# Main_Board_rev_A_-_hand_solder.net
KiCad netlist of a schematic drawn in EAGLE
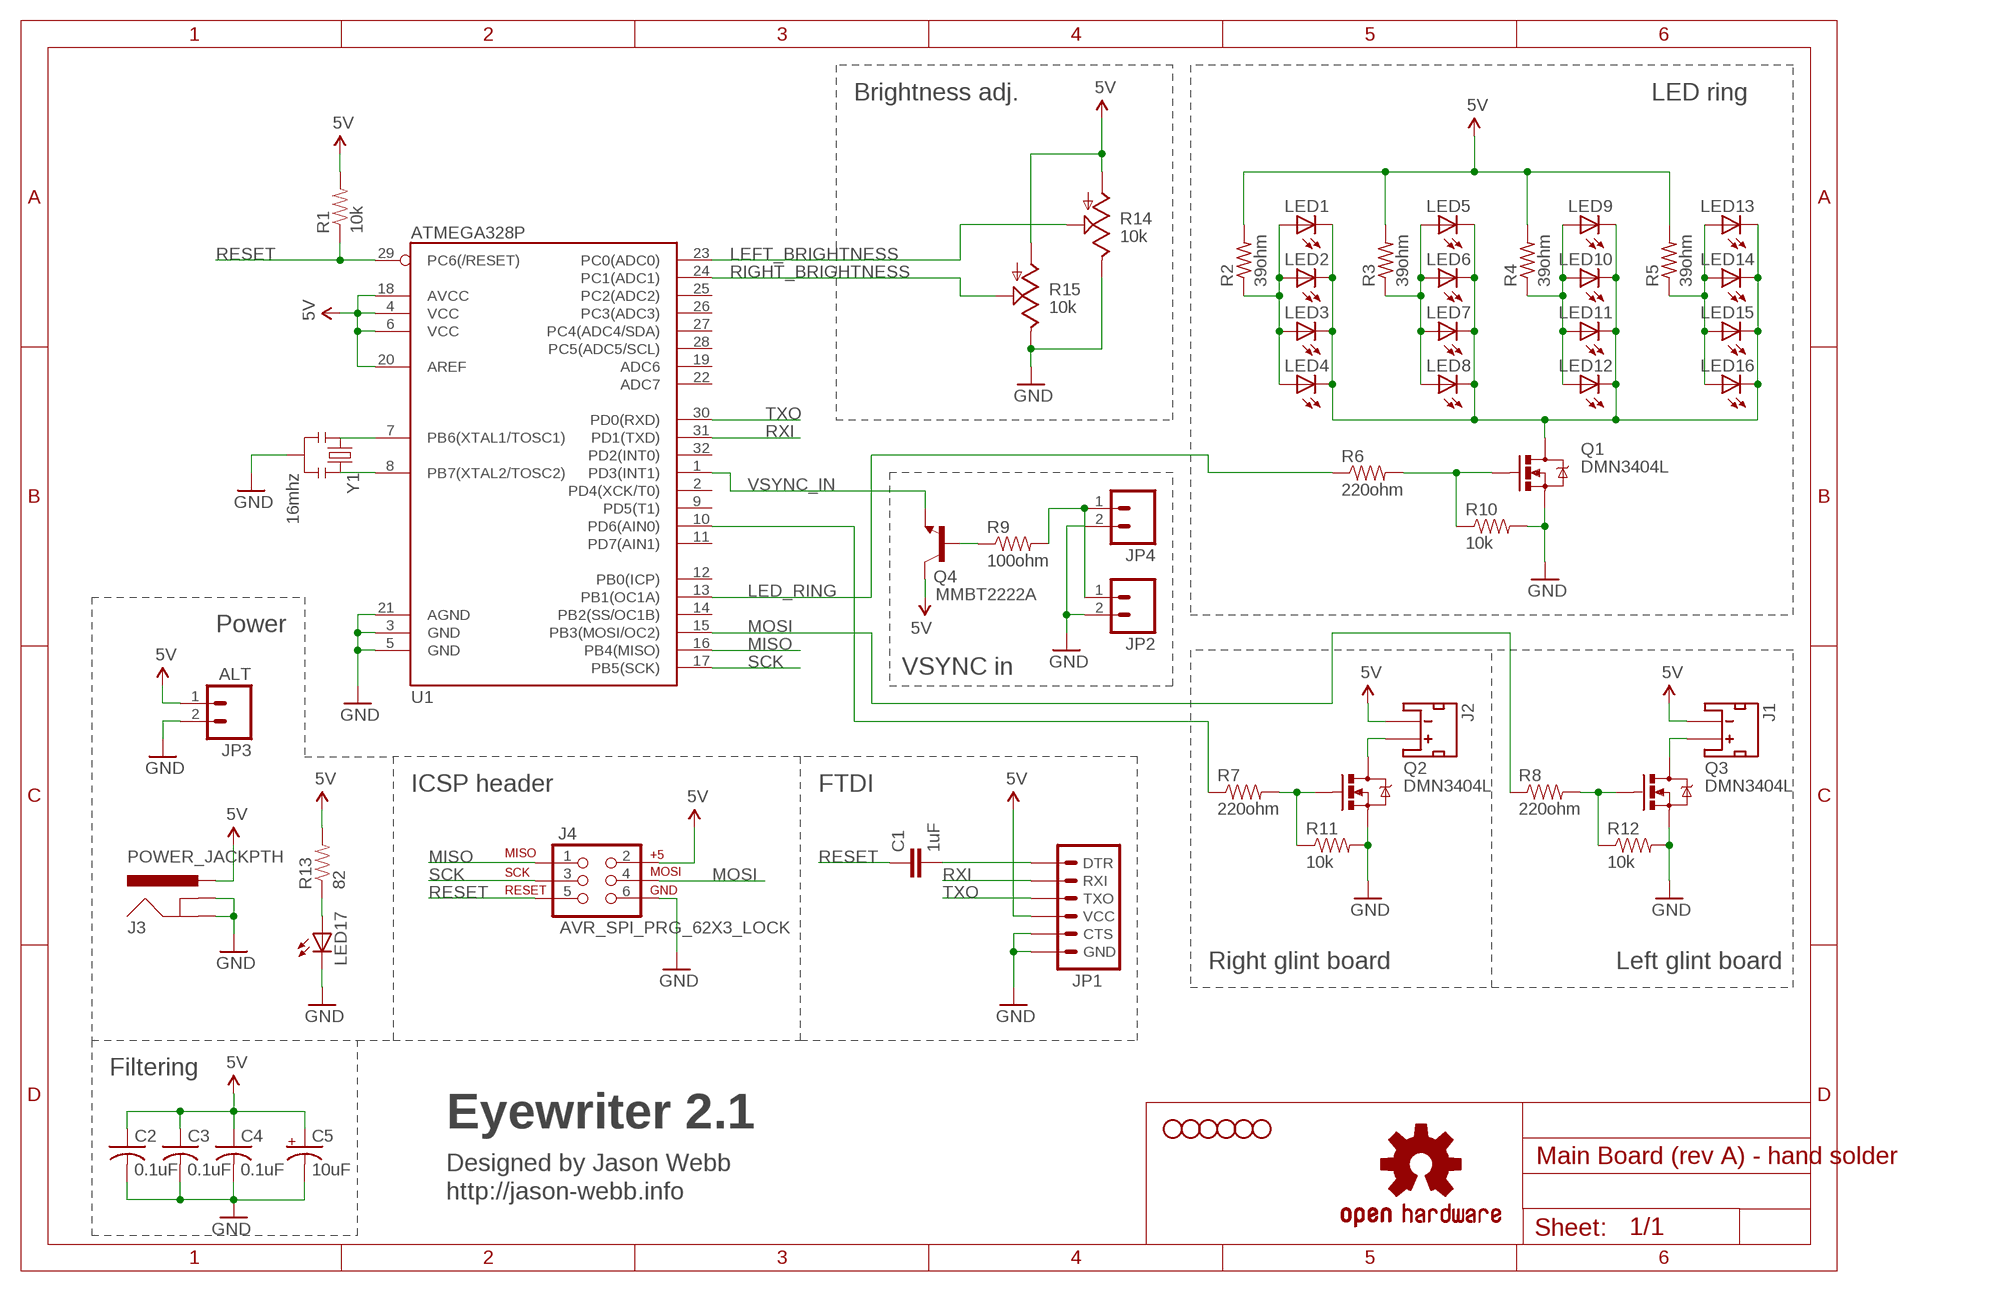
[diagram p0: schematic, sheet 1]

(export (version "E")
  (design (tool "Eeschema 10.0.6"))
  (components
    (comp (ref "C1")
      (value "1uF")
      (footprint "eagle-import:0805")
      (libsource (lib "eagle-import") (part "CAP0805"))
    )
    (comp (ref "C2")
      (value "0.1uF")
      (footprint "eagle-import:C0805K")
      (libsource (lib "eagle-import") (part "C-USC0805K"))
    )
    (comp (ref "C3")
      (value "0.1uF")
      (footprint "eagle-import:C0805K")
      (libsource (lib "eagle-import") (part "C-USC0805K"))
    )
    (comp (ref "C4")
      (value "0.1uF")
      (footprint "eagle-import:C0805K")
      (libsource (lib "eagle-import") (part "C-USC0805K"))
    )
    (comp (ref "C5")
      (value "10uF")
      (footprint "eagle-import:A_3216-18R")
      (libsource (lib "eagle-import") (part "CPOL-USA/3216-18R"))
    )
    (comp (ref "J1")
      (value "JST_2MM_MALE")
      (footprint "eagle-import:JST-2-SMD")
      (libsource (lib "eagle-import") (part "JST_2MM_MALE"))
    )
    (comp (ref "J2")
      (value "JST_2MM_MALE")
      (footprint "eagle-import:JST-2-SMD")
      (libsource (lib "eagle-import") (part "JST_2MM_MALE"))
    )
    (comp (ref "J3")
      (value "POWER_JACKPTH")
      (footprint "eagle-import:POWER_JACK_PTH")
      (libsource (lib "eagle-import") (part "POWER_JACKPTH"))
    )
    (comp (ref "J4")
      (value "AVR_SPI_PRG_62X3_LOCK")
      (footprint "eagle-import:2X3_LOCK")
      (libsource (lib "eagle-import") (part "AVR_SPI_PRG_62X3_LOCK"))
    )
    (comp (ref "JP1")
      (value "ARDUINO_SERIAL_PROGRAMLOCK")
      (footprint "eagle-import:1X06_LOCK")
      (libsource (lib "eagle-import") (part "ARDUINO_SERIAL_PROGRAMLOCK"))
    )
    (comp (ref "JP2")
      (value "M02PTH")
      (footprint "eagle-import:1X02")
      (libsource (lib "eagle-import") (part "M02PTH"))
    )
    (comp (ref "JP3")
      (value "ALT")
      (footprint "eagle-import:1X02")
      (libsource (lib "eagle-import") (part "M02PTH"))
    )
    (comp (ref "JP4")
      (value "M02PTH")
      (footprint "eagle-import:1X02")
      (libsource (lib "eagle-import") (part "M02PTH"))
    )
    (comp (ref "LED1")
      (value "LED5MM")
      (footprint "eagle-import:LED5MM")
      (libsource (lib "eagle-import") (part "LED5MM"))
    )
    (comp (ref "LED2")
      (value "LED5MM")
      (footprint "eagle-import:LED5MM")
      (libsource (lib "eagle-import") (part "LED5MM"))
    )
    (comp (ref "LED3")
      (value "LED5MM")
      (footprint "eagle-import:LED5MM")
      (libsource (lib "eagle-import") (part "LED5MM"))
    )
    (comp (ref "LED4")
      (value "LED5MM")
      (footprint "eagle-import:LED5MM")
      (libsource (lib "eagle-import") (part "LED5MM"))
    )
    (comp (ref "LED5")
      (value "LED5MM")
      (footprint "eagle-import:LED5MM")
      (libsource (lib "eagle-import") (part "LED5MM"))
    )
    (comp (ref "LED6")
      (value "LED5MM")
      (footprint "eagle-import:LED5MM")
      (libsource (lib "eagle-import") (part "LED5MM"))
    )
    (comp (ref "LED7")
      (value "LED5MM")
      (footprint "eagle-import:LED5MM")
      (libsource (lib "eagle-import") (part "LED5MM"))
    )
    (comp (ref "LED8")
      (value "LED5MM")
      (footprint "eagle-import:LED5MM")
      (libsource (lib "eagle-import") (part "LED5MM"))
    )
    (comp (ref "LED9")
      (value "LED5MM")
      (footprint "eagle-import:LED5MM")
      (libsource (lib "eagle-import") (part "LED5MM"))
    )
    (comp (ref "LED10")
      (value "LED5MM")
      (footprint "eagle-import:LED5MM")
      (libsource (lib "eagle-import") (part "LED5MM"))
    )
    (comp (ref "LED11")
      (value "LED5MM")
      (footprint "eagle-import:LED5MM")
      (libsource (lib "eagle-import") (part "LED5MM"))
    )
    (comp (ref "LED12")
      (value "LED5MM")
      (footprint "eagle-import:LED5MM")
      (libsource (lib "eagle-import") (part "LED5MM"))
    )
    (comp (ref "LED13")
      (value "LED5MM")
      (footprint "eagle-import:LED5MM")
      (libsource (lib "eagle-import") (part "LED5MM"))
    )
    (comp (ref "LED14")
      (value "LED5MM")
      (footprint "eagle-import:LED5MM")
      (libsource (lib "eagle-import") (part "LED5MM"))
    )
    (comp (ref "LED15")
      (value "LED5MM")
      (footprint "eagle-import:LED5MM")
      (libsource (lib "eagle-import") (part "LED5MM"))
    )
    (comp (ref "LED16")
      (value "LED5MM")
      (footprint "eagle-import:LED5MM")
      (libsource (lib "eagle-import") (part "LED5MM"))
    )
    (comp (ref "LED17")
      (value "LEDCHIPLED_0805")
      (footprint "eagle-import:CHIPLED_0805")
      (libsource (lib "eagle-import") (part "LEDCHIPLED_0805"))
    )
    (comp (ref "LOGO1")
      (value "OSHW-LOGOS")
      (footprint "eagle-import:OSHW-LOGO-S")
      (libsource (lib "eagle-import") (part "OSHW-LOGOS"))
    )
    (comp (ref "Q1")
      (value "DMN3404L")
      (footprint "eagle-import:SOT23-3")
      (libsource (lib "eagle-import") (part "MOSFET-NCHANNELSMD"))
    )
    (comp (ref "Q2")
      (value "DMN3404L")
      (footprint "eagle-import:SOT23-3")
      (libsource (lib "eagle-import") (part "MOSFET-NCHANNELSMD"))
    )
    (comp (ref "Q3")
      (value "DMN3404L")
      (footprint "eagle-import:SOT23-3")
      (libsource (lib "eagle-import") (part "MOSFET-NCHANNELSMD"))
    )
    (comp (ref "Q4")
      (value "MMBT2222A")
      (footprint "eagle-import:SOT23")
      (libsource (lib "eagle-import") (part "TRANSISTOR_NPNSOT23"))
    )
    (comp (ref "R1")
      (value "10k")
      (footprint "eagle-import:0805")
      (libsource (lib "eagle-import") (part "RESISTOR0805-RES"))
    )
    (comp (ref "R2")
      (value "39ohm")
      (footprint "eagle-import:0309_10")
      (libsource (lib "eagle-import") (part "R-US_0309/10"))
    )
    (comp (ref "R3")
      (value "39ohm")
      (footprint "eagle-import:0309_10")
      (libsource (lib "eagle-import") (part "R-US_0309/10"))
    )
    (comp (ref "R4")
      (value "39ohm")
      (footprint "eagle-import:0309_10")
      (libsource (lib "eagle-import") (part "R-US_0309/10"))
    )
    (comp (ref "R5")
      (value "39ohm")
      (footprint "eagle-import:0309_10")
      (libsource (lib "eagle-import") (part "R-US_0309/10"))
    )
    (comp (ref "R6")
      (value "220ohm")
      (footprint "eagle-import:0805")
      (libsource (lib "eagle-import") (part "RESISTOR0805-RES"))
    )
    (comp (ref "R7")
      (value "220ohm")
      (footprint "eagle-import:0805")
      (libsource (lib "eagle-import") (part "RESISTOR0805-RES"))
    )
    (comp (ref "R8")
      (value "220ohm")
      (footprint "eagle-import:0805")
      (libsource (lib "eagle-import") (part "RESISTOR0805-RES"))
    )
    (comp (ref "R9")
      (value "100ohm")
      (footprint "eagle-import:0805")
      (libsource (lib "eagle-import") (part "RESISTOR0805-RES"))
    )
    (comp (ref "R10")
      (value "10k")
      (footprint "eagle-import:0805")
      (libsource (lib "eagle-import") (part "RESISTOR0805-RES"))
    )
    (comp (ref "R11")
      (value "10k")
      (footprint "eagle-import:0805")
      (libsource (lib "eagle-import") (part "RESISTOR0805-RES"))
    )
    (comp (ref "R12")
      (value "10k")
      (footprint "eagle-import:0805")
      (libsource (lib "eagle-import") (part "RESISTOR0805-RES"))
    )
    (comp (ref "R13")
      (value "82")
      (footprint "eagle-import:0805")
      (libsource (lib "eagle-import") (part "RESISTOR0805-RES"))
    )
    (comp (ref "R14")
      (value "10k")
      (footprint "eagle-import:ALPS_POT")
      (libsource (lib "eagle-import") (part "POT"))
    )
    (comp (ref "R15")
      (value "10k")
      (footprint "eagle-import:ALPS_POT")
      (libsource (lib "eagle-import") (part "POT"))
    )
    (comp (ref "STANDOFF1")
      (value "STAND-OFF")
      (footprint "eagle-import:STAND-OFF")
      (libsource (lib "eagle-import") (part "STAND-OFF"))
    )
    (comp (ref "STANDOFF2")
      (value "STAND-OFF")
      (footprint "eagle-import:STAND-OFF")
      (libsource (lib "eagle-import") (part "STAND-OFF"))
    )
    (comp (ref "STANDOFF3")
      (value "STAND-OFF")
      (footprint "eagle-import:STAND-OFF")
      (libsource (lib "eagle-import") (part "STAND-OFF"))
    )
    (comp (ref "STANDOFF4")
      (value "STAND-OFF")
      (footprint "eagle-import:STAND-OFF")
      (libsource (lib "eagle-import") (part "STAND-OFF"))
    )
    (comp (ref "STANDOFF5")
      (value "STAND-OFF")
      (footprint "eagle-import:STAND-OFF")
      (libsource (lib "eagle-import") (part "STAND-OFF"))
    )
    (comp (ref "STANDOFF6")
      (value "STAND-OFF")
      (footprint "eagle-import:STAND-OFF")
      (libsource (lib "eagle-import") (part "STAND-OFF"))
    )
    (comp (ref "U1")
      (value "ATMEGA328P")
      (footprint "eagle-import:TQFP32-08")
      (libsource (lib "eagle-import") (part "ATMEGA328_SMT"))
    )
    (comp (ref "Y1")
      (value "16mhz")
      (footprint "eagle-import:RESONATOR-PTH")
      (libsource (lib "eagle-import") (part "RESONATORPTH"))
    )
  )
  (nets
    (net (code "1") (name "/LED_RING") (class "Default")
      (node (ref "R6") (pin "1") (pinfunction "1_1") (pintype "passive"))
      (node (ref "U1") (pin "13") (pinfunction "PB1(OC1A)_13") (pintype "bidirectional"))
    )
    (net (code "2") (name "/LEFT_BRIGHTNESS") (class "Default")
      (node (ref "R14") (pin "P$2") (pinfunction "S_P$2") (pintype "passive"))
      (node (ref "U1") (pin "23") (pinfunction "PC0(ADC0)_23") (pintype "bidirectional"))
    )
    (net (code "3") (name "/MISO") (class "Default")
      (node (ref "J4") (pin "1") (pinfunction "1_1") (pintype "passive"))
      (node (ref "U1") (pin "16") (pinfunction "PB4(MISO)_16") (pintype "bidirectional"))
    )
    (net (code "4") (name "/MOSI") (class "Default")
      (node (ref "J4") (pin "4") (pinfunction "4_4") (pintype "passive"))
      (node (ref "R7") (pin "1") (pinfunction "1_1") (pintype "passive"))
      (node (ref "U1") (pin "10") (pinfunction "PD6(AIN0)_10") (pintype "bidirectional"))
    )
    (net (code "5") (name "/RESET") (class "Default")
      (node (ref "C1") (pin "1") (pinfunction "1_1") (pintype "passive"))
      (node (ref "J4") (pin "5") (pinfunction "5_5") (pintype "passive"))
      (node (ref "R1") (pin "1") (pinfunction "1_1") (pintype "passive"))
      (node (ref "U1") (pin "29") (pinfunction "PC6(/RESET)_29") (pintype "bidirectional"))
    )
    (net (code "6") (name "/RIGHT_BRIGHTNESS") (class "Default")
      (node (ref "R15") (pin "P$2") (pinfunction "S_P$2") (pintype "passive"))
      (node (ref "U1") (pin "24") (pinfunction "PC1(ADC1)_24") (pintype "bidirectional"))
    )
    (net (code "7") (name "/RXI") (class "Default")
      (node (ref "JP1") (pin "2") (pinfunction "RXI_2") (pintype "passive"))
      (node (ref "U1") (pin "31") (pinfunction "PD1(TXD)_31") (pintype "bidirectional"))
    )
    (net (code "8") (name "/SCK") (class "Default")
      (node (ref "J4") (pin "3") (pinfunction "3_3") (pintype "passive"))
      (node (ref "U1") (pin "17") (pinfunction "PB5(SCK)_17") (pintype "bidirectional"))
    )
    (net (code "9") (name "/TXO") (class "Default")
      (node (ref "JP1") (pin "3") (pinfunction "TXO_3") (pintype "passive"))
      (node (ref "U1") (pin "30") (pinfunction "PD0(RXD)_30") (pintype "bidirectional"))
    )
    (net (code "10") (name "/VSYNC_IN") (class "Default")
      (node (ref "Q4") (pin "2") (pinfunction "E_2") (pintype "passive"))
      (node (ref "U1") (pin "1") (pinfunction "PD3(INT1)_1") (pintype "bidirectional"))
    )
    (net (code "11") (name "5V") (class "Default")
      (node (ref "C2") (pin "1") (pinfunction "1_1") (pintype "passive"))
      (node (ref "C3") (pin "1") (pinfunction "1_1") (pintype "passive"))
      (node (ref "C4") (pin "1") (pinfunction "1_1") (pintype "passive"))
      (node (ref "C5") (pin "+") (pinfunction "+_+") (pintype "passive"))
      (node (ref "J1") (pin "1") (pinfunction "-_1") (pintype "bidirectional"))
      (node (ref "J2") (pin "1") (pinfunction "-_1") (pintype "bidirectional"))
      (node (ref "J3") (pin "PWR") (pinfunction "PWR_PWR") (pintype "bidirectional"))
      (node (ref "J4") (pin "2") (pinfunction "2_2") (pintype "passive"))
      (node (ref "JP1") (pin "4") (pinfunction "VCC_4") (pintype "passive"))
      (node (ref "JP3") (pin "1") (pinfunction "1_1") (pintype "passive"))
      (node (ref "Q4") (pin "3") (pinfunction "C_3") (pintype "passive"))
      (node (ref "R1") (pin "2") (pinfunction "2_2") (pintype "passive"))
      (node (ref "R13") (pin "2") (pinfunction "2_2") (pintype "passive"))
      (node (ref "R14") (pin "P$3") (pinfunction "A_P$3") (pintype "passive"))
      (node (ref "R15") (pin "P$3") (pinfunction "A_P$3") (pintype "passive"))
      (node (ref "R2") (pin "2") (pinfunction "2_2") (pintype "passive"))
      (node (ref "R3") (pin "2") (pinfunction "2_2") (pintype "passive"))
      (node (ref "R4") (pin "2") (pinfunction "2_2") (pintype "passive"))
      (node (ref "R5") (pin "2") (pinfunction "2_2") (pintype "passive"))
      (node (ref "U1") (pin "18") (pinfunction "AVCC_18") (pintype "bidirectional"))
      (node (ref "U1") (pin "20") (pinfunction "AREF_20") (pintype "bidirectional"))
      (node (ref "U1") (pin "4") (pinfunction "VCC_4") (pintype "bidirectional"))
      (node (ref "U1") (pin "6") (pinfunction "VCC_6") (pintype "bidirectional"))
    )
    (net (code "12") (name "GND") (class "Default")
      (node (ref "C2") (pin "2") (pinfunction "2_2") (pintype "passive"))
      (node (ref "C3") (pin "2") (pinfunction "2_2") (pintype "passive"))
      (node (ref "C4") (pin "2") (pinfunction "2_2") (pintype "passive"))
      (node (ref "C5") (pin "-") (pinfunction "-_-") (pintype "passive"))
      (node (ref "J3") (pin "GND") (pinfunction "GND_GND") (pintype "bidirectional"))
      (node (ref "J3") (pin "GNDBREAK") (pinfunction "GNDBREAK_GNDBREAK") (pintype "bidirectional"))
      (node (ref "J4") (pin "6") (pinfunction "6_6") (pintype "passive"))
      (node (ref "JP1") (pin "5") (pinfunction "CTS_5") (pintype "passive"))
      (node (ref "JP1") (pin "6") (pinfunction "GND_6") (pintype "passive"))
      (node (ref "JP2") (pin "2") (pinfunction "2_2") (pintype "passive"))
      (node (ref "JP3") (pin "2") (pinfunction "2_2") (pintype "passive"))
      (node (ref "JP4") (pin "2") (pinfunction "2_2") (pintype "passive"))
      (node (ref "LED17") (pin "C") (pinfunction "C_C") (pintype "passive"))
      (node (ref "Q1") (pin "2") (pinfunction "S_2") (pintype "passive"))
      (node (ref "Q2") (pin "2") (pinfunction "S_2") (pintype "passive"))
      (node (ref "Q3") (pin "2") (pinfunction "S_2") (pintype "passive"))
      (node (ref "R10") (pin "2") (pinfunction "2_2") (pintype "passive"))
      (node (ref "R11") (pin "2") (pinfunction "2_2") (pintype "passive"))
      (node (ref "R12") (pin "2") (pinfunction "2_2") (pintype "passive"))
      (node (ref "R14") (pin "P$1") (pinfunction "E_P$1") (pintype "passive"))
      (node (ref "R15") (pin "P$1") (pinfunction "E_P$1") (pintype "passive"))
      (node (ref "U1") (pin "21") (pinfunction "AGND_21") (pintype "bidirectional"))
      (node (ref "U1") (pin "3") (pinfunction "GND_3") (pintype "bidirectional"))
      (node (ref "U1") (pin "5") (pinfunction "GND_5") (pintype "bidirectional"))
      (node (ref "Y1") (pin "2") (pinfunction "2_2") (pintype "passive"))
    )
    (net (code "13") (name "Net-(J1-+)") (class "Default")
      (node (ref "J1") (pin "2") (pinfunction "+_2") (pintype "bidirectional"))
      (node (ref "Q3") (pin "3") (pinfunction "D_3") (pintype "passive"))
    )
    (net (code "14") (name "Net-(J2-+)") (class "Default")
      (node (ref "J2") (pin "2") (pinfunction "+_2") (pintype "bidirectional"))
      (node (ref "Q2") (pin "3") (pinfunction "D_3") (pintype "passive"))
    )
    (net (code "15") (name "Net-(JP1-DTR)") (class "Default")
      (node (ref "C1") (pin "2") (pinfunction "2_2") (pintype "passive"))
      (node (ref "JP1") (pin "1") (pinfunction "DTR_1") (pintype "passive"))
    )
    (net (code "16") (name "Net-(JP2-Pad1)") (class "Default")
      (node (ref "JP2") (pin "1") (pinfunction "1_1") (pintype "passive"))
      (node (ref "JP4") (pin "1") (pinfunction "1_1") (pintype "passive"))
      (node (ref "R9") (pin "2") (pinfunction "2_2") (pintype "passive"))
    )
    (net (code "17") (name "Net-(LED1-C)") (class "Default")
      (node (ref "LED1") (pin "K") (pinfunction "C_K") (pintype "passive"))
      (node (ref "LED10") (pin "K") (pinfunction "C_K") (pintype "passive"))
      (node (ref "LED11") (pin "K") (pinfunction "C_K") (pintype "passive"))
      (node (ref "LED12") (pin "K") (pinfunction "C_K") (pintype "passive"))
      (node (ref "LED13") (pin "K") (pinfunction "C_K") (pintype "passive"))
      (node (ref "LED14") (pin "K") (pinfunction "C_K") (pintype "passive"))
      (node (ref "LED15") (pin "K") (pinfunction "C_K") (pintype "passive"))
      (node (ref "LED16") (pin "K") (pinfunction "C_K") (pintype "passive"))
      (node (ref "LED2") (pin "K") (pinfunction "C_K") (pintype "passive"))
      (node (ref "LED3") (pin "K") (pinfunction "C_K") (pintype "passive"))
      (node (ref "LED4") (pin "K") (pinfunction "C_K") (pintype "passive"))
      (node (ref "LED5") (pin "K") (pinfunction "C_K") (pintype "passive"))
      (node (ref "LED6") (pin "K") (pinfunction "C_K") (pintype "passive"))
      (node (ref "LED7") (pin "K") (pinfunction "C_K") (pintype "passive"))
      (node (ref "LED8") (pin "K") (pinfunction "C_K") (pintype "passive"))
      (node (ref "LED9") (pin "K") (pinfunction "C_K") (pintype "passive"))
      (node (ref "Q1") (pin "3") (pinfunction "D_3") (pintype "passive"))
    )
    (net (code "18") (name "Net-(LED1-PadA)") (class "Default")
      (node (ref "LED1") (pin "A") (pinfunction "A_A") (pintype "passive"))
      (node (ref "LED2") (pin "A") (pinfunction "A_A") (pintype "passive"))
      (node (ref "LED3") (pin "A") (pinfunction "A_A") (pintype "passive"))
      (node (ref "LED4") (pin "A") (pinfunction "A_A") (pintype "passive"))
      (node (ref "R2") (pin "1") (pinfunction "1_1") (pintype "passive"))
    )
    (net (code "19") (name "Net-(LED5-PadA)") (class "Default")
      (node (ref "LED5") (pin "A") (pinfunction "A_A") (pintype "passive"))
      (node (ref "LED6") (pin "A") (pinfunction "A_A") (pintype "passive"))
      (node (ref "LED7") (pin "A") (pinfunction "A_A") (pintype "passive"))
      (node (ref "LED8") (pin "A") (pinfunction "A_A") (pintype "passive"))
      (node (ref "R3") (pin "1") (pinfunction "1_1") (pintype "passive"))
    )
    (net (code "20") (name "Net-(LED10-PadA)") (class "Default")
      (node (ref "LED10") (pin "A") (pinfunction "A_A") (pintype "passive"))
      (node (ref "LED11") (pin "A") (pinfunction "A_A") (pintype "passive"))
      (node (ref "LED12") (pin "A") (pinfunction "A_A") (pintype "passive"))
      (node (ref "LED9") (pin "A") (pinfunction "A_A") (pintype "passive"))
      (node (ref "R4") (pin "1") (pinfunction "1_1") (pintype "passive"))
    )
    (net (code "21") (name "Net-(LED13-PadA)") (class "Default")
      (node (ref "LED13") (pin "A") (pinfunction "A_A") (pintype "passive"))
      (node (ref "LED14") (pin "A") (pinfunction "A_A") (pintype "passive"))
      (node (ref "LED15") (pin "A") (pinfunction "A_A") (pintype "passive"))
      (node (ref "LED16") (pin "A") (pinfunction "A_A") (pintype "passive"))
      (node (ref "R5") (pin "1") (pinfunction "1_1") (pintype "passive"))
    )
    (net (code "22") (name "Net-(LED17-PadA)") (class "Default")
      (node (ref "LED17") (pin "A") (pinfunction "A_A") (pintype "passive"))
      (node (ref "R13") (pin "1") (pinfunction "1_1") (pintype "passive"))
    )
    (net (code "23") (name "Net-(Q1-G)") (class "Default")
      (node (ref "Q1") (pin "1") (pinfunction "G_1") (pintype "passive"))
      (node (ref "R10") (pin "1") (pinfunction "1_1") (pintype "passive"))
      (node (ref "R6") (pin "2") (pinfunction "2_2") (pintype "passive"))
    )
    (net (code "24") (name "Net-(Q2-G)") (class "Default")
      (node (ref "Q2") (pin "1") (pinfunction "G_1") (pintype "passive"))
      (node (ref "R11") (pin "1") (pinfunction "1_1") (pintype "passive"))
      (node (ref "R7") (pin "2") (pinfunction "2_2") (pintype "passive"))
    )
    (net (code "25") (name "Net-(Q3-G)") (class "Default")
      (node (ref "Q3") (pin "1") (pinfunction "G_1") (pintype "passive"))
      (node (ref "R12") (pin "1") (pinfunction "1_1") (pintype "passive"))
      (node (ref "R8") (pin "2") (pinfunction "2_2") (pintype "passive"))
    )
    (net (code "26") (name "Net-(Q4-B)") (class "Default")
      (node (ref "Q4") (pin "1") (pinfunction "B_1") (pintype "passive"))
      (node (ref "R9") (pin "1") (pinfunction "1_1") (pintype "passive"))
    )
    (net (code "27") (name "Net-(U1-PB3(MOSI{slash}OC2))") (class "Default")
      (node (ref "R8") (pin "1") (pinfunction "1_1") (pintype "passive"))
      (node (ref "U1") (pin "15") (pinfunction "PB3(MOSI/OC2)_15") (pintype "bidirectional"))
    )
    (net (code "28") (name "Net-(U1-PB6(XTAL1{slash}TOSC1))") (class "Default")
      (node (ref "U1") (pin "7") (pinfunction "PB6(XTAL1/TOSC1)_7") (pintype "bidirectional"))
      (node (ref "Y1") (pin "1") (pinfunction "1_1") (pintype "passive"))
    )
    (net (code "29") (name "Net-(U1-PB7(XTAL2{slash}TOSC2))") (class "Default")
      (node (ref "U1") (pin "8") (pinfunction "PB7(XTAL2/TOSC2)_8") (pintype "bidirectional"))
      (node (ref "Y1") (pin "3") (pinfunction "3_3") (pintype "passive"))
    )
    (net (code "30") (name "unconnected-(J1-PAD1-PadNC1)") (class "Default")
      (node (ref "J1") (pin "NC1") (pinfunction "PAD1_NC1") (pintype "bidirectional"))
    )
    (net (code "31") (name "unconnected-(J1-PAD2-PadNC2)") (class "Default")
      (node (ref "J1") (pin "NC2") (pinfunction "PAD2_NC2") (pintype "bidirectional"))
    )
    (net (code "32") (name "unconnected-(J2-PAD1-PadNC1)") (class "Default")
      (node (ref "J2") (pin "NC1") (pinfunction "PAD1_NC1") (pintype "bidirectional"))
    )
    (net (code "33") (name "unconnected-(J2-PAD2-PadNC2)") (class "Default")
      (node (ref "J2") (pin "NC2") (pinfunction "PAD2_NC2") (pintype "bidirectional"))
    )
    (net (code "34") (name "unconnected-(U1-ADC6-Pad19)") (class "Default")
      (node (ref "U1") (pin "19") (pinfunction "ADC6_19") (pintype "bidirectional"))
    )
    (net (code "35") (name "unconnected-(U1-ADC7-Pad22)") (class "Default")
      (node (ref "U1") (pin "22") (pinfunction "ADC7_22") (pintype "bidirectional"))
    )
    (net (code "36") (name "unconnected-(U1-PB0(ICP)-Pad12)") (class "Default")
      (node (ref "U1") (pin "12") (pinfunction "PB0(ICP)_12") (pintype "bidirectional"))
    )
    (net (code "37") (name "unconnected-(U1-PB2(SS{slash}OC1B)-Pad14)") (class "Default")
      (node (ref "U1") (pin "14") (pinfunction "PB2(SS/OC1B)_14") (pintype "bidirectional"))
    )
    (net (code "38") (name "unconnected-(U1-PC2(ADC2)-Pad25)") (class "Default")
      (node (ref "U1") (pin "25") (pinfunction "PC2(ADC2)_25") (pintype "bidirectional"))
    )
    (net (code "39") (name "unconnected-(U1-PC3(ADC3)-Pad26)") (class "Default")
      (node (ref "U1") (pin "26") (pinfunction "PC3(ADC3)_26") (pintype "bidirectional"))
    )
    (net (code "40") (name "unconnected-(U1-PC4(ADC4{slash}SDA)-Pad27)") (class "Default")
      (node (ref "U1") (pin "27") (pinfunction "PC4(ADC4/SDA)_27") (pintype "bidirectional"))
    )
    (net (code "41") (name "unconnected-(U1-PC5(ADC5{slash}SCL)-Pad28)") (class "Default")
      (node (ref "U1") (pin "28") (pinfunction "PC5(ADC5/SCL)_28") (pintype "bidirectional"))
    )
    (net (code "42") (name "unconnected-(U1-PD2(INT0)-Pad32)") (class "Default")
      (node (ref "U1") (pin "32") (pinfunction "PD2(INT0)_32") (pintype "bidirectional"))
    )
    (net (code "43") (name "unconnected-(U1-PD4(XCK{slash}T0)-Pad2)") (class "Default")
      (node (ref "U1") (pin "2") (pinfunction "PD4(XCK/T0)_2") (pintype "bidirectional"))
    )
    (net (code "44") (name "unconnected-(U1-PD5(T1)-Pad9)") (class "Default")
      (node (ref "U1") (pin "9") (pinfunction "PD5(T1)_9") (pintype "bidirectional"))
    )
    (net (code "45") (name "unconnected-(U1-PD7(AIN1)-Pad11)") (class "Default")
      (node (ref "U1") (pin "11") (pinfunction "PD7(AIN1)_11") (pintype "bidirectional"))
    )
  )
)
